# MiniBus.net
KiCad netlist of a schematic drawn in EAGLE
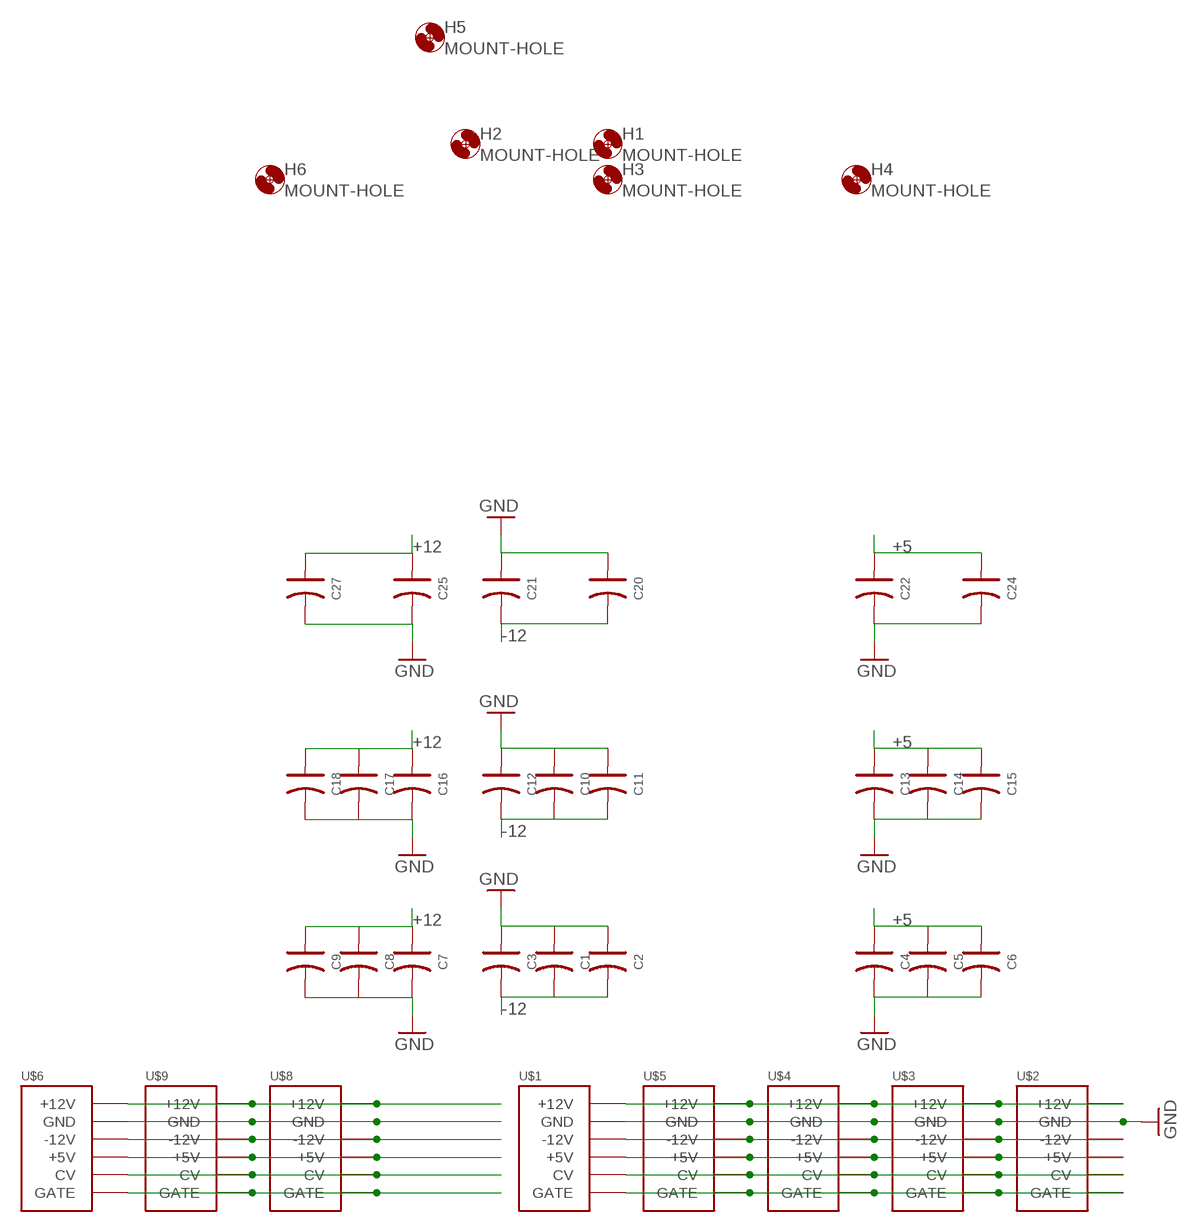
[diagram p0: schematic, sheet 1]

(export (version "E")
  (design (tool "Eeschema 10.0.6"))
  (components
    (comp (ref "C1")
      (value "C-POLAR-A")
      (footprint "eagle-import:AVX-A")
      (libsource (lib "eagle-import") (part "C-POLAR-A"))
    )
    (comp (ref "C2")
      (value "C-POLAR-A")
      (footprint "eagle-import:AVX-A")
      (libsource (lib "eagle-import") (part "C-POLAR-A"))
    )
    (comp (ref "C3")
      (value "C-POLAR-A")
      (footprint "eagle-import:AVX-A")
      (libsource (lib "eagle-import") (part "C-POLAR-A"))
    )
    (comp (ref "C4")
      (value "C-POLAR-A")
      (footprint "eagle-import:AVX-A")
      (libsource (lib "eagle-import") (part "C-POLAR-A"))
    )
    (comp (ref "C5")
      (value "C-POLAR-A")
      (footprint "eagle-import:AVX-A")
      (libsource (lib "eagle-import") (part "C-POLAR-A"))
    )
    (comp (ref "C6")
      (value "C-POLAR-A")
      (footprint "eagle-import:AVX-A")
      (libsource (lib "eagle-import") (part "C-POLAR-A"))
    )
    (comp (ref "C7")
      (value "C-POLAR-A")
      (footprint "eagle-import:AVX-A")
      (libsource (lib "eagle-import") (part "C-POLAR-A"))
    )
    (comp (ref "C8")
      (value "C-POLAR-A")
      (footprint "eagle-import:AVX-A")
      (libsource (lib "eagle-import") (part "C-POLAR-A"))
    )
    (comp (ref "C9")
      (value "C-POLAR-A")
      (footprint "eagle-import:AVX-A")
      (libsource (lib "eagle-import") (part "C-POLAR-A"))
    )
    (comp (ref "C10")
      (value "C-POLAR-A")
      (footprint "eagle-import:AVX-A")
      (libsource (lib "eagle-import") (part "C-POLAR-A"))
    )
    (comp (ref "C11")
      (value "C-POLAR-A")
      (footprint "eagle-import:AVX-A")
      (libsource (lib "eagle-import") (part "C-POLAR-A"))
    )
    (comp (ref "C12")
      (value "C-POLAR-A")
      (footprint "eagle-import:AVX-A")
      (libsource (lib "eagle-import") (part "C-POLAR-A"))
    )
    (comp (ref "C13")
      (value "C-POLAR-A")
      (footprint "eagle-import:AVX-A")
      (libsource (lib "eagle-import") (part "C-POLAR-A"))
    )
    (comp (ref "C14")
      (value "C-POLAR-A")
      (footprint "eagle-import:AVX-A")
      (libsource (lib "eagle-import") (part "C-POLAR-A"))
    )
    (comp (ref "C15")
      (value "C-POLAR-A")
      (footprint "eagle-import:AVX-A")
      (libsource (lib "eagle-import") (part "C-POLAR-A"))
    )
    (comp (ref "C16")
      (value "C-POLAR-A")
      (footprint "eagle-import:AVX-A")
      (libsource (lib "eagle-import") (part "C-POLAR-A"))
    )
    (comp (ref "C17")
      (value "C-POLAR-A")
      (footprint "eagle-import:AVX-A")
      (libsource (lib "eagle-import") (part "C-POLAR-A"))
    )
    (comp (ref "C18")
      (value "C-POLAR-A")
      (footprint "eagle-import:AVX-A")
      (libsource (lib "eagle-import") (part "C-POLAR-A"))
    )
    (comp (ref "C20")
      (value "C-POLAR-A")
      (footprint "eagle-import:AVX-A")
      (libsource (lib "eagle-import") (part "C-POLAR-A"))
    )
    (comp (ref "C21")
      (value "C-POLAR-A")
      (footprint "eagle-import:AVX-A")
      (libsource (lib "eagle-import") (part "C-POLAR-A"))
    )
    (comp (ref "C22")
      (value "C-POLAR-A")
      (footprint "eagle-import:AVX-A")
      (libsource (lib "eagle-import") (part "C-POLAR-A"))
    )
    (comp (ref "C24")
      (value "C-POLAR-A")
      (footprint "eagle-import:AVX-A")
      (libsource (lib "eagle-import") (part "C-POLAR-A"))
    )
    (comp (ref "C25")
      (value "C-POLAR-A")
      (footprint "eagle-import:AVX-A")
      (libsource (lib "eagle-import") (part "C-POLAR-A"))
    )
    (comp (ref "C27")
      (value "C-POLAR-A")
      (footprint "eagle-import:AVX-A")
      (libsource (lib "eagle-import") (part "C-POLAR-A"))
    )
    (comp (ref "H1")
      (value "MOUNT-HOLE")
      (footprint "eagle-import:3.2-NOMARKINGS-SMALLSAFEZONE")
      (libsource (lib "eagle-import") (part "MOUNT-HOLE"))
    )
    (comp (ref "H2")
      (value "MOUNT-HOLE")
      (footprint "eagle-import:3.2-NOMARKINGS-SMALLSAFEZONE")
      (libsource (lib "eagle-import") (part "MOUNT-HOLE"))
    )
    (comp (ref "H3")
      (value "MOUNT-HOLE")
      (footprint "eagle-import:3.2-NOMARKINGS-SMALLSAFEZONE")
      (libsource (lib "eagle-import") (part "MOUNT-HOLE"))
    )
    (comp (ref "H4")
      (value "MOUNT-HOLE")
      (footprint "eagle-import:3.2-NOMARKINGS-SMALLSAFEZONE")
      (libsource (lib "eagle-import") (part "MOUNT-HOLE"))
    )
    (comp (ref "H5")
      (value "MOUNT-HOLE")
      (footprint "eagle-import:3.2-NOMARKINGS-SMALLSAFEZONE")
      (libsource (lib "eagle-import") (part "MOUNT-HOLE"))
    )
    (comp (ref "H6")
      (value "MOUNT-HOLE")
      (footprint "eagle-import:3.2-NOMARKINGS-SMALLSAFEZONE")
      (libsource (lib "eagle-import") (part "MOUNT-HOLE"))
    )
    (comp (ref "U$1")
      (value "POWER")
      (footprint "eagle-import:POWER_16")
      (libsource (lib "eagle-import") (part "POWER"))
    )
    (comp (ref "U$2")
      (value "POWER")
      (footprint "eagle-import:POWER_16")
      (libsource (lib "eagle-import") (part "POWER"))
    )
    (comp (ref "U$3")
      (value "POWER")
      (footprint "eagle-import:POWER_16")
      (libsource (lib "eagle-import") (part "POWER"))
    )
    (comp (ref "U$4")
      (value "POWER")
      (footprint "eagle-import:POWER_16")
      (libsource (lib "eagle-import") (part "POWER"))
    )
    (comp (ref "U$5")
      (value "POWER")
      (footprint "eagle-import:POWER_16")
      (libsource (lib "eagle-import") (part "POWER"))
    )
    (comp (ref "U$6")
      (value "POWER")
      (footprint "eagle-import:POWER_16")
      (libsource (lib "eagle-import") (part "POWER"))
    )
    (comp (ref "U$8")
      (value "POWER")
      (footprint "eagle-import:POWER_16")
      (libsource (lib "eagle-import") (part "POWER"))
    )
    (comp (ref "U$9")
      (value "POWER")
      (footprint "eagle-import:POWER_16")
      (libsource (lib "eagle-import") (part "POWER"))
    )
  )
  (nets
    (net (code "1") (name "/+5") (class "Default")
      (node (ref "C13") (pin "+") (pinfunction "1_+") (pintype "bidirectional"))
      (node (ref "C14") (pin "+") (pinfunction "1_+") (pintype "bidirectional"))
      (node (ref "C15") (pin "+") (pinfunction "1_+") (pintype "bidirectional"))
      (node (ref "C22") (pin "+") (pinfunction "1_+") (pintype "bidirectional"))
      (node (ref "C24") (pin "+") (pinfunction "1_+") (pintype "bidirectional"))
      (node (ref "C4") (pin "+") (pinfunction "1_+") (pintype "bidirectional"))
      (node (ref "C5") (pin "+") (pinfunction "1_+") (pintype "bidirectional"))
      (node (ref "C6") (pin "+") (pinfunction "1_+") (pintype "bidirectional"))
      (node (ref "U$1") (pin "11") (pinfunction "+5V_11") (pintype "bidirectional"))
      (node (ref "U$1") (pin "12") (pinfunction "+5V_12") (pintype "bidirectional"))
      (node (ref "U$2") (pin "11") (pinfunction "+5V_11") (pintype "bidirectional"))
      (node (ref "U$2") (pin "12") (pinfunction "+5V_12") (pintype "bidirectional"))
      (node (ref "U$3") (pin "11") (pinfunction "+5V_11") (pintype "bidirectional"))
      (node (ref "U$3") (pin "12") (pinfunction "+5V_12") (pintype "bidirectional"))
      (node (ref "U$4") (pin "11") (pinfunction "+5V_11") (pintype "bidirectional"))
      (node (ref "U$4") (pin "12") (pinfunction "+5V_12") (pintype "bidirectional"))
      (node (ref "U$5") (pin "11") (pinfunction "+5V_11") (pintype "bidirectional"))
      (node (ref "U$5") (pin "12") (pinfunction "+5V_12") (pintype "bidirectional"))
      (node (ref "U$6") (pin "11") (pinfunction "+5V_11") (pintype "bidirectional"))
      (node (ref "U$6") (pin "12") (pinfunction "+5V_12") (pintype "bidirectional"))
      (node (ref "U$8") (pin "11") (pinfunction "+5V_11") (pintype "bidirectional"))
      (node (ref "U$8") (pin "12") (pinfunction "+5V_12") (pintype "bidirectional"))
      (node (ref "U$9") (pin "11") (pinfunction "+5V_11") (pintype "bidirectional"))
      (node (ref "U$9") (pin "12") (pinfunction "+5V_12") (pintype "bidirectional"))
    )
    (net (code "2") (name "/+12") (class "Default")
      (node (ref "C16") (pin "+") (pinfunction "1_+") (pintype "bidirectional"))
      (node (ref "C17") (pin "+") (pinfunction "1_+") (pintype "bidirectional"))
      (node (ref "C18") (pin "+") (pinfunction "1_+") (pintype "bidirectional"))
      (node (ref "C25") (pin "+") (pinfunction "1_+") (pintype "bidirectional"))
      (node (ref "C27") (pin "+") (pinfunction "1_+") (pintype "bidirectional"))
      (node (ref "C7") (pin "+") (pinfunction "1_+") (pintype "bidirectional"))
      (node (ref "C8") (pin "+") (pinfunction "1_+") (pintype "bidirectional"))
      (node (ref "C9") (pin "+") (pinfunction "1_+") (pintype "bidirectional"))
      (node (ref "U$1") (pin "10") (pinfunction "+12V_10") (pintype "bidirectional"))
      (node (ref "U$1") (pin "9") (pinfunction "+12V_9") (pintype "bidirectional"))
      (node (ref "U$2") (pin "10") (pinfunction "+12V_10") (pintype "bidirectional"))
      (node (ref "U$2") (pin "9") (pinfunction "+12V_9") (pintype "bidirectional"))
      (node (ref "U$3") (pin "10") (pinfunction "+12V_10") (pintype "bidirectional"))
      (node (ref "U$3") (pin "9") (pinfunction "+12V_9") (pintype "bidirectional"))
      (node (ref "U$4") (pin "10") (pinfunction "+12V_10") (pintype "bidirectional"))
      (node (ref "U$4") (pin "9") (pinfunction "+12V_9") (pintype "bidirectional"))
      (node (ref "U$5") (pin "10") (pinfunction "+12V_10") (pintype "bidirectional"))
      (node (ref "U$5") (pin "9") (pinfunction "+12V_9") (pintype "bidirectional"))
      (node (ref "U$6") (pin "10") (pinfunction "+12V_10") (pintype "bidirectional"))
      (node (ref "U$6") (pin "9") (pinfunction "+12V_9") (pintype "bidirectional"))
      (node (ref "U$8") (pin "10") (pinfunction "+12V_10") (pintype "bidirectional"))
      (node (ref "U$8") (pin "9") (pinfunction "+12V_9") (pintype "bidirectional"))
      (node (ref "U$9") (pin "10") (pinfunction "+12V_10") (pintype "bidirectional"))
      (node (ref "U$9") (pin "9") (pinfunction "+12V_9") (pintype "bidirectional"))
    )
    (net (code "3") (name "/-12") (class "Default")
      (node (ref "C1") (pin "-") (pinfunction "2_-") (pintype "bidirectional"))
      (node (ref "C10") (pin "-") (pinfunction "2_-") (pintype "bidirectional"))
      (node (ref "C11") (pin "-") (pinfunction "2_-") (pintype "bidirectional"))
      (node (ref "C12") (pin "-") (pinfunction "2_-") (pintype "bidirectional"))
      (node (ref "C2") (pin "-") (pinfunction "2_-") (pintype "bidirectional"))
      (node (ref "C20") (pin "-") (pinfunction "2_-") (pintype "bidirectional"))
      (node (ref "C21") (pin "-") (pinfunction "2_-") (pintype "bidirectional"))
      (node (ref "C3") (pin "-") (pinfunction "2_-") (pintype "bidirectional"))
      (node (ref "U$1") (pin "1") (pinfunction "-12V_1") (pintype "bidirectional"))
      (node (ref "U$1") (pin "2") (pinfunction "-12V_2") (pintype "bidirectional"))
      (node (ref "U$2") (pin "1") (pinfunction "-12V_1") (pintype "bidirectional"))
      (node (ref "U$2") (pin "2") (pinfunction "-12V_2") (pintype "bidirectional"))
      (node (ref "U$3") (pin "1") (pinfunction "-12V_1") (pintype "bidirectional"))
      (node (ref "U$3") (pin "2") (pinfunction "-12V_2") (pintype "bidirectional"))
      (node (ref "U$4") (pin "1") (pinfunction "-12V_1") (pintype "bidirectional"))
      (node (ref "U$4") (pin "2") (pinfunction "-12V_2") (pintype "bidirectional"))
      (node (ref "U$5") (pin "1") (pinfunction "-12V_1") (pintype "bidirectional"))
      (node (ref "U$5") (pin "2") (pinfunction "-12V_2") (pintype "bidirectional"))
      (node (ref "U$6") (pin "1") (pinfunction "-12V_1") (pintype "bidirectional"))
      (node (ref "U$6") (pin "2") (pinfunction "-12V_2") (pintype "bidirectional"))
      (node (ref "U$8") (pin "1") (pinfunction "-12V_1") (pintype "bidirectional"))
      (node (ref "U$8") (pin "2") (pinfunction "-12V_2") (pintype "bidirectional"))
      (node (ref "U$9") (pin "1") (pinfunction "-12V_1") (pintype "bidirectional"))
      (node (ref "U$9") (pin "2") (pinfunction "-12V_2") (pintype "bidirectional"))
    )
    (net (code "4") (name "/CV") (class "Default")
      (node (ref "U$1") (pin "13") (pinfunction "CV_13") (pintype "bidirectional"))
      (node (ref "U$1") (pin "14") (pinfunction "CV_14") (pintype "bidirectional"))
      (node (ref "U$2") (pin "13") (pinfunction "CV_13") (pintype "bidirectional"))
      (node (ref "U$2") (pin "14") (pinfunction "CV_14") (pintype "bidirectional"))
      (node (ref "U$3") (pin "13") (pinfunction "CV_13") (pintype "bidirectional"))
      (node (ref "U$3") (pin "14") (pinfunction "CV_14") (pintype "bidirectional"))
      (node (ref "U$4") (pin "13") (pinfunction "CV_13") (pintype "bidirectional"))
      (node (ref "U$4") (pin "14") (pinfunction "CV_14") (pintype "bidirectional"))
      (node (ref "U$5") (pin "13") (pinfunction "CV_13") (pintype "bidirectional"))
      (node (ref "U$5") (pin "14") (pinfunction "CV_14") (pintype "bidirectional"))
      (node (ref "U$6") (pin "13") (pinfunction "CV_13") (pintype "bidirectional"))
      (node (ref "U$6") (pin "14") (pinfunction "CV_14") (pintype "bidirectional"))
      (node (ref "U$8") (pin "13") (pinfunction "CV_13") (pintype "bidirectional"))
      (node (ref "U$8") (pin "14") (pinfunction "CV_14") (pintype "bidirectional"))
      (node (ref "U$9") (pin "13") (pinfunction "CV_13") (pintype "bidirectional"))
      (node (ref "U$9") (pin "14") (pinfunction "CV_14") (pintype "bidirectional"))
    )
    (net (code "5") (name "/GATE") (class "Default")
      (node (ref "U$1") (pin "15") (pinfunction "GATE_15") (pintype "bidirectional"))
      (node (ref "U$1") (pin "16") (pinfunction "GATE_16") (pintype "bidirectional"))
      (node (ref "U$2") (pin "15") (pinfunction "GATE_15") (pintype "bidirectional"))
      (node (ref "U$2") (pin "16") (pinfunction "GATE_16") (pintype "bidirectional"))
      (node (ref "U$3") (pin "15") (pinfunction "GATE_15") (pintype "bidirectional"))
      (node (ref "U$3") (pin "16") (pinfunction "GATE_16") (pintype "bidirectional"))
      (node (ref "U$4") (pin "15") (pinfunction "GATE_15") (pintype "bidirectional"))
      (node (ref "U$4") (pin "16") (pinfunction "GATE_16") (pintype "bidirectional"))
      (node (ref "U$5") (pin "15") (pinfunction "GATE_15") (pintype "bidirectional"))
      (node (ref "U$5") (pin "16") (pinfunction "GATE_16") (pintype "bidirectional"))
      (node (ref "U$6") (pin "15") (pinfunction "GATE_15") (pintype "bidirectional"))
      (node (ref "U$6") (pin "16") (pinfunction "GATE_16") (pintype "bidirectional"))
      (node (ref "U$8") (pin "15") (pinfunction "GATE_15") (pintype "bidirectional"))
      (node (ref "U$8") (pin "16") (pinfunction "GATE_16") (pintype "bidirectional"))
      (node (ref "U$9") (pin "15") (pinfunction "GATE_15") (pintype "bidirectional"))
      (node (ref "U$9") (pin "16") (pinfunction "GATE_16") (pintype "bidirectional"))
    )
    (net (code "6") (name "GND") (class "Default")
      (node (ref "C1") (pin "+") (pinfunction "1_+") (pintype "bidirectional"))
      (node (ref "C10") (pin "+") (pinfunction "1_+") (pintype "bidirectional"))
      (node (ref "C11") (pin "+") (pinfunction "1_+") (pintype "bidirectional"))
      (node (ref "C12") (pin "+") (pinfunction "1_+") (pintype "bidirectional"))
      (node (ref "C13") (pin "-") (pinfunction "2_-") (pintype "bidirectional"))
      (node (ref "C14") (pin "-") (pinfunction "2_-") (pintype "bidirectional"))
      (node (ref "C15") (pin "-") (pinfunction "2_-") (pintype "bidirectional"))
      (node (ref "C16") (pin "-") (pinfunction "2_-") (pintype "bidirectional"))
      (node (ref "C17") (pin "-") (pinfunction "2_-") (pintype "bidirectional"))
      (node (ref "C18") (pin "-") (pinfunction "2_-") (pintype "bidirectional"))
      (node (ref "C2") (pin "+") (pinfunction "1_+") (pintype "bidirectional"))
      (node (ref "C20") (pin "+") (pinfunction "1_+") (pintype "bidirectional"))
      (node (ref "C21") (pin "+") (pinfunction "1_+") (pintype "bidirectional"))
      (node (ref "C22") (pin "-") (pinfunction "2_-") (pintype "bidirectional"))
      (node (ref "C24") (pin "-") (pinfunction "2_-") (pintype "bidirectional"))
      (node (ref "C25") (pin "-") (pinfunction "2_-") (pintype "bidirectional"))
      (node (ref "C27") (pin "-") (pinfunction "2_-") (pintype "bidirectional"))
      (node (ref "C3") (pin "+") (pinfunction "1_+") (pintype "bidirectional"))
      (node (ref "C4") (pin "-") (pinfunction "2_-") (pintype "bidirectional"))
      (node (ref "C5") (pin "-") (pinfunction "2_-") (pintype "bidirectional"))
      (node (ref "C6") (pin "-") (pinfunction "2_-") (pintype "bidirectional"))
      (node (ref "C7") (pin "-") (pinfunction "2_-") (pintype "bidirectional"))
      (node (ref "C8") (pin "-") (pinfunction "2_-") (pintype "bidirectional"))
      (node (ref "C9") (pin "-") (pinfunction "2_-") (pintype "bidirectional"))
      (node (ref "U$1") (pin "3") (pinfunction "GND_3") (pintype "bidirectional"))
      (node (ref "U$1") (pin "4") (pinfunction "GND_4") (pintype "bidirectional"))
      (node (ref "U$1") (pin "5") (pinfunction "GND_5") (pintype "bidirectional"))
      (node (ref "U$1") (pin "6") (pinfunction "GND_6") (pintype "bidirectional"))
      (node (ref "U$1") (pin "7") (pinfunction "GND_7") (pintype "bidirectional"))
      (node (ref "U$1") (pin "8") (pinfunction "GND_8") (pintype "bidirectional"))
      (node (ref "U$2") (pin "3") (pinfunction "GND_3") (pintype "bidirectional"))
      (node (ref "U$2") (pin "4") (pinfunction "GND_4") (pintype "bidirectional"))
      (node (ref "U$2") (pin "5") (pinfunction "GND_5") (pintype "bidirectional"))
      (node (ref "U$2") (pin "6") (pinfunction "GND_6") (pintype "bidirectional"))
      (node (ref "U$2") (pin "7") (pinfunction "GND_7") (pintype "bidirectional"))
      (node (ref "U$2") (pin "8") (pinfunction "GND_8") (pintype "bidirectional"))
      (node (ref "U$3") (pin "3") (pinfunction "GND_3") (pintype "bidirectional"))
      (node (ref "U$3") (pin "4") (pinfunction "GND_4") (pintype "bidirectional"))
      (node (ref "U$3") (pin "5") (pinfunction "GND_5") (pintype "bidirectional"))
      (node (ref "U$3") (pin "6") (pinfunction "GND_6") (pintype "bidirectional"))
      (node (ref "U$3") (pin "7") (pinfunction "GND_7") (pintype "bidirectional"))
      (node (ref "U$3") (pin "8") (pinfunction "GND_8") (pintype "bidirectional"))
      (node (ref "U$4") (pin "3") (pinfunction "GND_3") (pintype "bidirectional"))
      (node (ref "U$4") (pin "4") (pinfunction "GND_4") (pintype "bidirectional"))
      (node (ref "U$4") (pin "5") (pinfunction "GND_5") (pintype "bidirectional"))
      (node (ref "U$4") (pin "6") (pinfunction "GND_6") (pintype "bidirectional"))
      (node (ref "U$4") (pin "7") (pinfunction "GND_7") (pintype "bidirectional"))
      (node (ref "U$4") (pin "8") (pinfunction "GND_8") (pintype "bidirectional"))
      (node (ref "U$5") (pin "3") (pinfunction "GND_3") (pintype "bidirectional"))
      (node (ref "U$5") (pin "4") (pinfunction "GND_4") (pintype "bidirectional"))
      (node (ref "U$5") (pin "5") (pinfunction "GND_5") (pintype "bidirectional"))
      (node (ref "U$5") (pin "6") (pinfunction "GND_6") (pintype "bidirectional"))
      (node (ref "U$5") (pin "7") (pinfunction "GND_7") (pintype "bidirectional"))
      (node (ref "U$5") (pin "8") (pinfunction "GND_8") (pintype "bidirectional"))
      (node (ref "U$6") (pin "3") (pinfunction "GND_3") (pintype "bidirectional"))
      (node (ref "U$6") (pin "4") (pinfunction "GND_4") (pintype "bidirectional"))
      (node (ref "U$6") (pin "5") (pinfunction "GND_5") (pintype "bidirectional"))
      (node (ref "U$6") (pin "6") (pinfunction "GND_6") (pintype "bidirectional"))
      (node (ref "U$6") (pin "7") (pinfunction "GND_7") (pintype "bidirectional"))
      (node (ref "U$6") (pin "8") (pinfunction "GND_8") (pintype "bidirectional"))
      (node (ref "U$8") (pin "3") (pinfunction "GND_3") (pintype "bidirectional"))
      (node (ref "U$8") (pin "4") (pinfunction "GND_4") (pintype "bidirectional"))
      (node (ref "U$8") (pin "5") (pinfunction "GND_5") (pintype "bidirectional"))
      (node (ref "U$8") (pin "6") (pinfunction "GND_6") (pintype "bidirectional"))
      (node (ref "U$8") (pin "7") (pinfunction "GND_7") (pintype "bidirectional"))
      (node (ref "U$8") (pin "8") (pinfunction "GND_8") (pintype "bidirectional"))
      (node (ref "U$9") (pin "3") (pinfunction "GND_3") (pintype "bidirectional"))
      (node (ref "U$9") (pin "4") (pinfunction "GND_4") (pintype "bidirectional"))
      (node (ref "U$9") (pin "5") (pinfunction "GND_5") (pintype "bidirectional"))
      (node (ref "U$9") (pin "6") (pinfunction "GND_6") (pintype "bidirectional"))
      (node (ref "U$9") (pin "7") (pinfunction "GND_7") (pintype "bidirectional"))
      (node (ref "U$9") (pin "8") (pinfunction "GND_8") (pintype "bidirectional"))
    )
  )
)
